# R601X.net
KiCad netlist of a schematic drawn in EAGLE
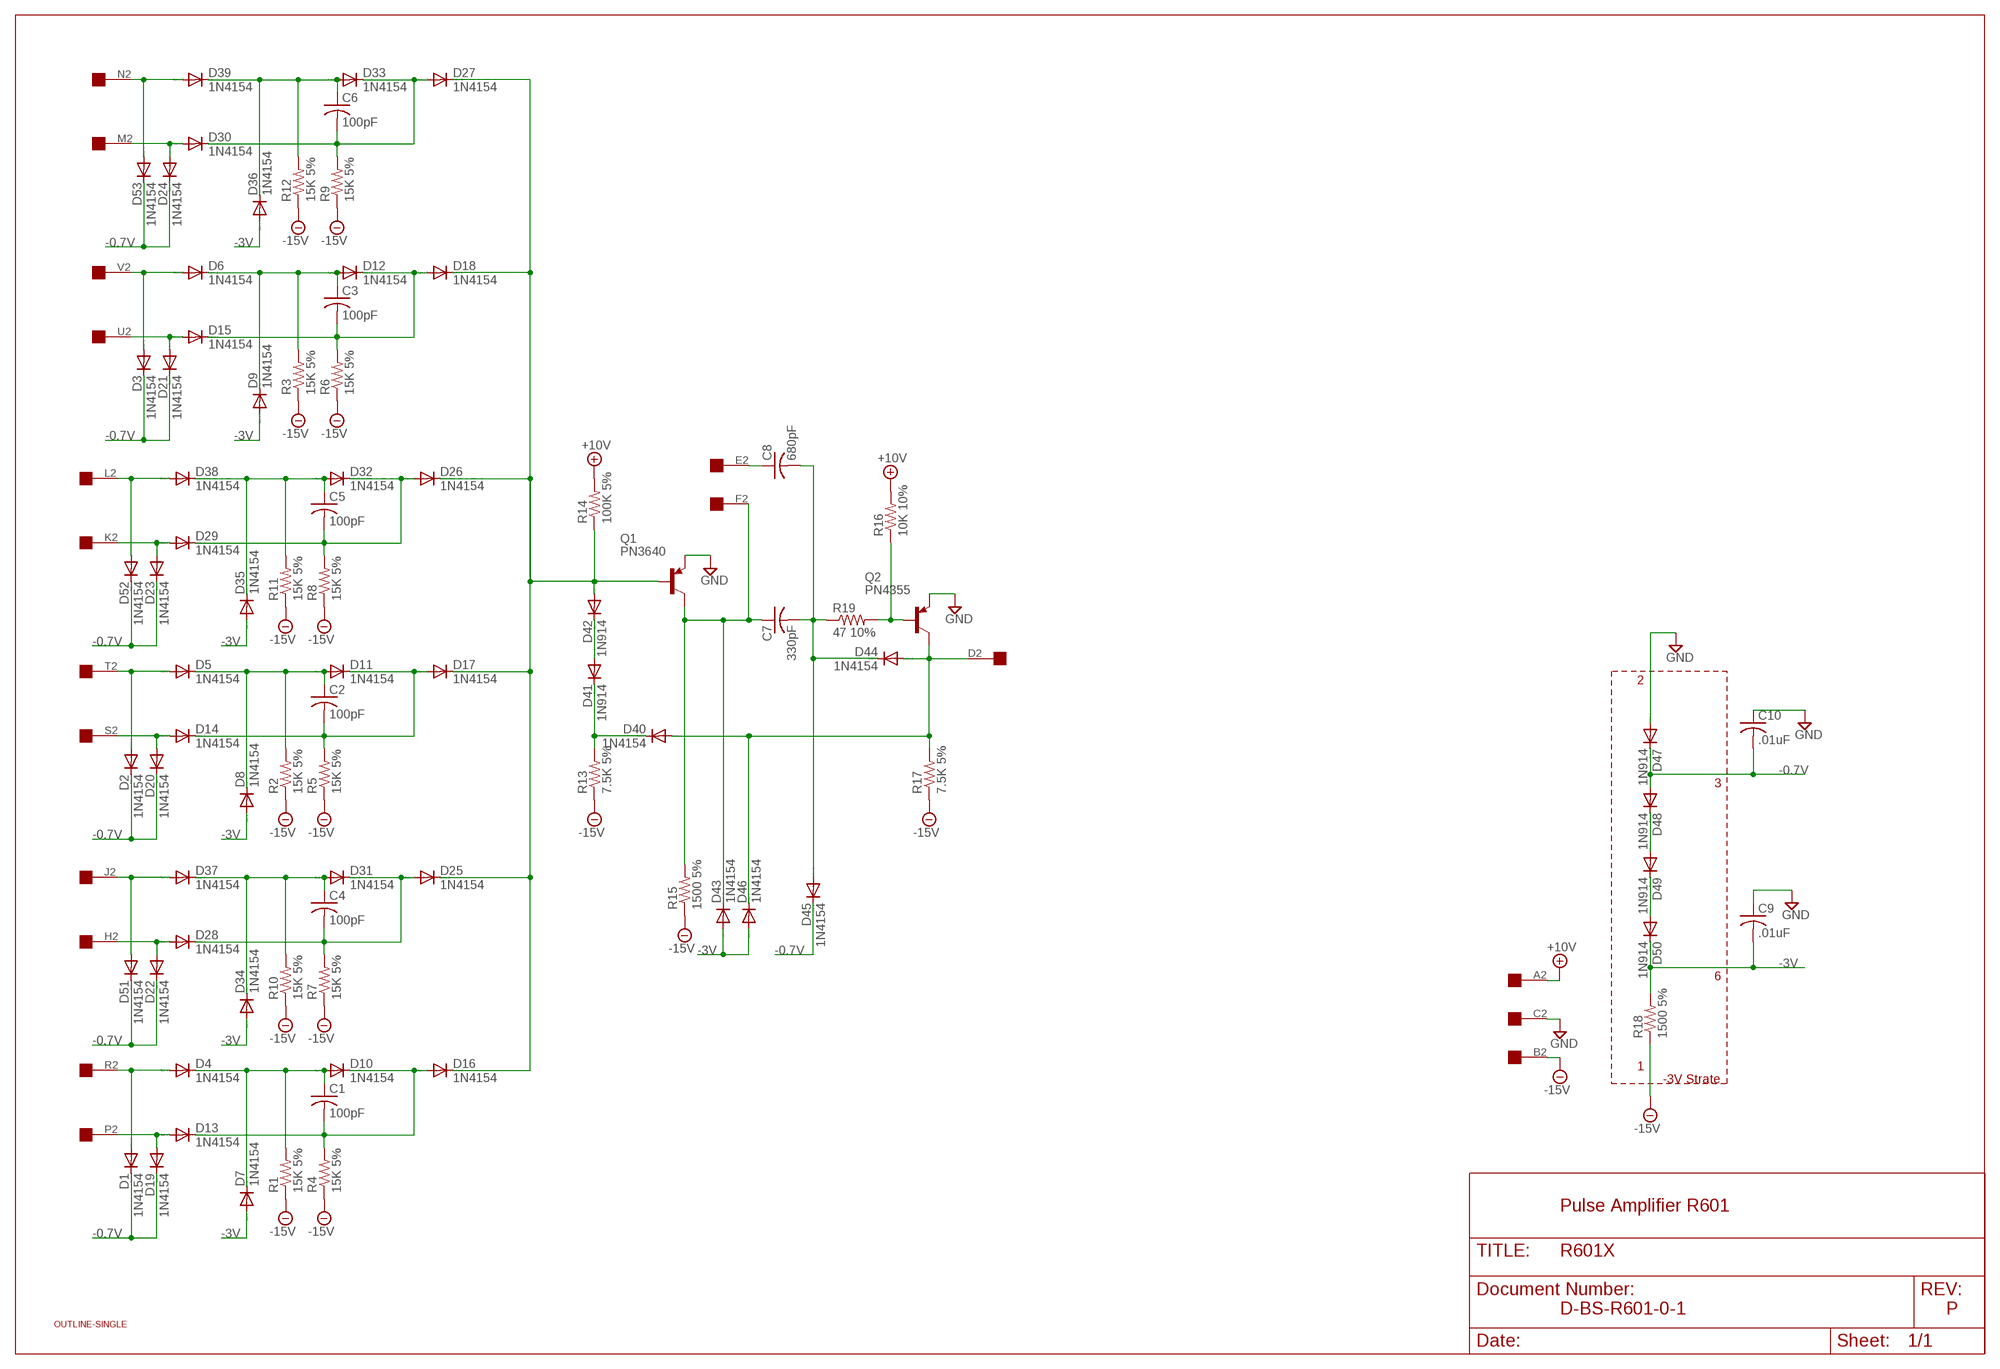
[diagram p0: schematic, sheet 1]

(export (version "E")
  (design (tool "Eeschema 10.0.6"))
  (components
    (comp (ref "C1")
      (value "100pF")
      (footprint "eagle-import:C050-025X075")
      (libsource (lib "eagle-import") (part "C-US050-025X075"))
    )
    (comp (ref "C2")
      (value "100pF")
      (footprint "eagle-import:C050-025X075")
      (libsource (lib "eagle-import") (part "C-US050-025X075"))
    )
    (comp (ref "C3")
      (value "100pF")
      (footprint "eagle-import:C050-025X075")
      (libsource (lib "eagle-import") (part "C-US050-025X075"))
    )
    (comp (ref "C4")
      (value "100pF")
      (footprint "eagle-import:C050-025X075")
      (libsource (lib "eagle-import") (part "C-US050-025X075"))
    )
    (comp (ref "C5")
      (value "100pF")
      (footprint "eagle-import:C050-025X075")
      (libsource (lib "eagle-import") (part "C-US050-025X075"))
    )
    (comp (ref "C6")
      (value "100pF")
      (footprint "eagle-import:C050-025X075")
      (libsource (lib "eagle-import") (part "C-US050-025X075"))
    )
    (comp (ref "C7")
      (value "330pF")
      (footprint "eagle-import:C050-025X075")
      (libsource (lib "eagle-import") (part "C-US050-025X075"))
    )
    (comp (ref "C8")
      (value "680pF")
      (footprint "eagle-import:C050-025X075")
      (libsource (lib "eagle-import") (part "C-US050-025X075"))
    )
    (comp (ref "C9")
      (value ".01uF")
      (footprint "eagle-import:C050-025X075")
      (libsource (lib "eagle-import") (part "C-US050-025X075"))
    )
    (comp (ref "C10")
      (value ".01uF")
      (footprint "eagle-import:C050-025X075")
      (libsource (lib "eagle-import") (part "C-US050-025X075"))
    )
    (comp (ref "D1")
      (value "1N4154")
      (footprint "eagle-import:DO35-10")
      (libsource (lib "eagle-import") (part "1N4148DO35-10"))
    )
    (comp (ref "D2")
      (value "1N4154")
      (footprint "eagle-import:DO35-10")
      (libsource (lib "eagle-import") (part "1N4148DO35-10"))
    )
    (comp (ref "D3")
      (value "1N4154")
      (footprint "eagle-import:DO35-10")
      (libsource (lib "eagle-import") (part "1N4148DO35-10"))
    )
    (comp (ref "D4")
      (value "1N4154")
      (footprint "eagle-import:DO35-10")
      (libsource (lib "eagle-import") (part "1N4148DO35-10"))
    )
    (comp (ref "D5")
      (value "1N4154")
      (footprint "eagle-import:DO35-10")
      (libsource (lib "eagle-import") (part "1N4148DO35-10"))
    )
    (comp (ref "D6")
      (value "1N4154")
      (footprint "eagle-import:DO35-10")
      (libsource (lib "eagle-import") (part "1N4148DO35-10"))
    )
    (comp (ref "D7")
      (value "1N4154")
      (footprint "eagle-import:DO35-10")
      (libsource (lib "eagle-import") (part "1N4148DO35-10"))
    )
    (comp (ref "D8")
      (value "1N4154")
      (footprint "eagle-import:DO35-10")
      (libsource (lib "eagle-import") (part "1N4148DO35-10"))
    )
    (comp (ref "D9")
      (value "1N4154")
      (footprint "eagle-import:DO35-10")
      (libsource (lib "eagle-import") (part "1N4148DO35-10"))
    )
    (comp (ref "D10")
      (value "1N4154")
      (footprint "eagle-import:DO35-10")
      (libsource (lib "eagle-import") (part "1N4148DO35-10"))
    )
    (comp (ref "D11")
      (value "1N4154")
      (footprint "eagle-import:DO35-10")
      (libsource (lib "eagle-import") (part "1N4148DO35-10"))
    )
    (comp (ref "D12")
      (value "1N4154")
      (footprint "eagle-import:DO35-10")
      (libsource (lib "eagle-import") (part "1N4148DO35-10"))
    )
    (comp (ref "D13")
      (value "1N4154")
      (footprint "eagle-import:DO35-10")
      (libsource (lib "eagle-import") (part "1N4148DO35-10"))
    )
    (comp (ref "D14")
      (value "1N4154")
      (footprint "eagle-import:DO35-10")
      (libsource (lib "eagle-import") (part "1N4148DO35-10"))
    )
    (comp (ref "D15")
      (value "1N4154")
      (footprint "eagle-import:DO35-10")
      (libsource (lib "eagle-import") (part "1N4148DO35-10"))
    )
    (comp (ref "D16")
      (value "1N4154")
      (footprint "eagle-import:DO35-10")
      (libsource (lib "eagle-import") (part "1N4148DO35-10"))
    )
    (comp (ref "D17")
      (value "1N4154")
      (footprint "eagle-import:DO35-10")
      (libsource (lib "eagle-import") (part "1N4148DO35-10"))
    )
    (comp (ref "D18")
      (value "1N4154")
      (footprint "eagle-import:DO35-10")
      (libsource (lib "eagle-import") (part "1N4148DO35-10"))
    )
    (comp (ref "D19")
      (value "1N4154")
      (footprint "eagle-import:DO35-10")
      (libsource (lib "eagle-import") (part "1N4148DO35-10"))
    )
    (comp (ref "D20")
      (value "1N4154")
      (footprint "eagle-import:DO35-10")
      (libsource (lib "eagle-import") (part "1N4148DO35-10"))
    )
    (comp (ref "D21")
      (value "1N4154")
      (footprint "eagle-import:DO35-10")
      (libsource (lib "eagle-import") (part "1N4148DO35-10"))
    )
    (comp (ref "D22")
      (value "1N4154")
      (footprint "eagle-import:DO35-10")
      (libsource (lib "eagle-import") (part "1N4148DO35-10"))
    )
    (comp (ref "D23")
      (value "1N4154")
      (footprint "eagle-import:DO35-10")
      (libsource (lib "eagle-import") (part "1N4148DO35-10"))
    )
    (comp (ref "D24")
      (value "1N4154")
      (footprint "eagle-import:DO35-10")
      (libsource (lib "eagle-import") (part "1N4148DO35-10"))
    )
    (comp (ref "D25")
      (value "1N4154")
      (footprint "eagle-import:DO35-10")
      (libsource (lib "eagle-import") (part "1N4148DO35-10"))
    )
    (comp (ref "D26")
      (value "1N4154")
      (footprint "eagle-import:DO35-10")
      (libsource (lib "eagle-import") (part "1N4148DO35-10"))
    )
    (comp (ref "D27")
      (value "1N4154")
      (footprint "eagle-import:DO35-10")
      (libsource (lib "eagle-import") (part "1N4148DO35-10"))
    )
    (comp (ref "D28")
      (value "1N4154")
      (footprint "eagle-import:DO35-10")
      (libsource (lib "eagle-import") (part "1N4148DO35-10"))
    )
    (comp (ref "D29")
      (value "1N4154")
      (footprint "eagle-import:DO35-10")
      (libsource (lib "eagle-import") (part "1N4148DO35-10"))
    )
    (comp (ref "D30")
      (value "1N4154")
      (footprint "eagle-import:DO35-10")
      (libsource (lib "eagle-import") (part "1N4148DO35-10"))
    )
    (comp (ref "D31")
      (value "1N4154")
      (footprint "eagle-import:DO35-10")
      (libsource (lib "eagle-import") (part "1N4148DO35-10"))
    )
    (comp (ref "D32")
      (value "1N4154")
      (footprint "eagle-import:DO35-10")
      (libsource (lib "eagle-import") (part "1N4148DO35-10"))
    )
    (comp (ref "D33")
      (value "1N4154")
      (footprint "eagle-import:DO35-10")
      (libsource (lib "eagle-import") (part "1N4148DO35-10"))
    )
    (comp (ref "D34")
      (value "1N4154")
      (footprint "eagle-import:DO35-10")
      (libsource (lib "eagle-import") (part "1N4148DO35-10"))
    )
    (comp (ref "D35")
      (value "1N4154")
      (footprint "eagle-import:DO35-10")
      (libsource (lib "eagle-import") (part "1N4148DO35-10"))
    )
    (comp (ref "D36")
      (value "1N4154")
      (footprint "eagle-import:DO35-10")
      (libsource (lib "eagle-import") (part "1N4148DO35-10"))
    )
    (comp (ref "D37")
      (value "1N4154")
      (footprint "eagle-import:DO35-10")
      (libsource (lib "eagle-import") (part "1N4148DO35-10"))
    )
    (comp (ref "D38")
      (value "1N4154")
      (footprint "eagle-import:DO35-10")
      (libsource (lib "eagle-import") (part "1N4148DO35-10"))
    )
    (comp (ref "D39")
      (value "1N4154")
      (footprint "eagle-import:DO35-10")
      (libsource (lib "eagle-import") (part "1N4148DO35-10"))
    )
    (comp (ref "D40")
      (value "1N4154")
      (footprint "eagle-import:DO35-10")
      (libsource (lib "eagle-import") (part "1N4148DO35-10"))
    )
    (comp (ref "D41")
      (value "1N914")
      (footprint "eagle-import:DO35-10")
      (libsource (lib "eagle-import") (part "1N4148DO35-10"))
    )
    (comp (ref "D42")
      (value "1N914")
      (footprint "eagle-import:DO35-10")
      (libsource (lib "eagle-import") (part "1N4148DO35-10"))
    )
    (comp (ref "D43")
      (value "1N4154")
      (footprint "eagle-import:DO35-10")
      (libsource (lib "eagle-import") (part "1N4148DO35-10"))
    )
    (comp (ref "D44")
      (value "1N4154")
      (footprint "eagle-import:DO35-10")
      (libsource (lib "eagle-import") (part "1N4148DO35-10"))
    )
    (comp (ref "D45")
      (value "1N4154")
      (footprint "eagle-import:DO35-10")
      (libsource (lib "eagle-import") (part "1N4148DO35-10"))
    )
    (comp (ref "D46")
      (value "1N4154")
      (footprint "eagle-import:DO35-10")
      (libsource (lib "eagle-import") (part "1N4148DO35-10"))
    )
    (comp (ref "D47")
      (value "1N914")
      (footprint "eagle-import:DO35-10")
      (libsource (lib "eagle-import") (part "1N4148DO35-10"))
    )
    (comp (ref "D48")
      (value "1N914")
      (footprint "eagle-import:DO35-10")
      (libsource (lib "eagle-import") (part "1N4148DO35-10"))
    )
    (comp (ref "D49")
      (value "1N914")
      (footprint "eagle-import:DO35-10")
      (libsource (lib "eagle-import") (part "1N4148DO35-10"))
    )
    (comp (ref "D50")
      (value "1N914")
      (footprint "eagle-import:DO35-10")
      (libsource (lib "eagle-import") (part "1N4148DO35-10"))
    )
    (comp (ref "D51")
      (value "1N4154")
      (footprint "eagle-import:DO35-10")
      (libsource (lib "eagle-import") (part "1N4148DO35-10"))
    )
    (comp (ref "D52")
      (value "1N4154")
      (footprint "eagle-import:DO35-10")
      (libsource (lib "eagle-import") (part "1N4148DO35-10"))
    )
    (comp (ref "D53")
      (value "1N4154")
      (footprint "eagle-import:DO35-10")
      (libsource (lib "eagle-import") (part "1N4148DO35-10"))
    )
    (comp (ref "Q1")
      (value "PN3640")
      (footprint "eagle-import:TO39")
      (libsource (lib "eagle-import") (part "2N2904"))
    )
    (comp (ref "Q2")
      (value "PN4355")
      (footprint "eagle-import:TO39")
      (libsource (lib "eagle-import") (part "2N2904"))
    )
    (comp (ref "R1")
      (value "15K 5%")
      (footprint "eagle-import:0207_10")
      (libsource (lib "eagle-import") (part "R-US_0207/10"))
    )
    (comp (ref "R2")
      (value "15K 5%")
      (footprint "eagle-import:0207_10")
      (libsource (lib "eagle-import") (part "R-US_0207/10"))
    )
    (comp (ref "R3")
      (value "15K 5%")
      (footprint "eagle-import:0207_10")
      (libsource (lib "eagle-import") (part "R-US_0207/10"))
    )
    (comp (ref "R4")
      (value "15K 5%")
      (footprint "eagle-import:0207_10")
      (libsource (lib "eagle-import") (part "R-US_0207/10"))
    )
    (comp (ref "R5")
      (value "15K 5%")
      (footprint "eagle-import:0207_10")
      (libsource (lib "eagle-import") (part "R-US_0207/10"))
    )
    (comp (ref "R6")
      (value "15K 5%")
      (footprint "eagle-import:0207_10")
      (libsource (lib "eagle-import") (part "R-US_0207/10"))
    )
    (comp (ref "R7")
      (value "15K 5%")
      (footprint "eagle-import:0207_10")
      (libsource (lib "eagle-import") (part "R-US_0207/10"))
    )
    (comp (ref "R8")
      (value "15K 5%")
      (footprint "eagle-import:0207_10")
      (libsource (lib "eagle-import") (part "R-US_0207/10"))
    )
    (comp (ref "R9")
      (value "15K 5%")
      (footprint "eagle-import:0207_10")
      (libsource (lib "eagle-import") (part "R-US_0207/10"))
    )
    (comp (ref "R10")
      (value "15K 5%")
      (footprint "eagle-import:0207_10")
      (libsource (lib "eagle-import") (part "R-US_0207/10"))
    )
    (comp (ref "R11")
      (value "15K 5%")
      (footprint "eagle-import:0207_10")
      (libsource (lib "eagle-import") (part "R-US_0207/10"))
    )
    (comp (ref "R12")
      (value "15K 5%")
      (footprint "eagle-import:0207_10")
      (libsource (lib "eagle-import") (part "R-US_0207/10"))
    )
    (comp (ref "R13")
      (value "7.5K 5%")
      (footprint "eagle-import:0207_10")
      (libsource (lib "eagle-import") (part "R-US_0207/10"))
    )
    (comp (ref "R14")
      (value "100K 5%")
      (footprint "eagle-import:0207_10")
      (libsource (lib "eagle-import") (part "R-US_0207/10"))
    )
    (comp (ref "R15")
      (value "1500 5%")
      (footprint "eagle-import:0207_10")
      (libsource (lib "eagle-import") (part "R-US_0207/10"))
    )
    (comp (ref "R16")
      (value "10K 10%")
      (footprint "eagle-import:0207_10")
      (libsource (lib "eagle-import") (part "R-US_0207/10"))
    )
    (comp (ref "R17")
      (value "7.5K 5%")
      (footprint "eagle-import:0207_10")
      (libsource (lib "eagle-import") (part "R-US_0207/10"))
    )
    (comp (ref "R18")
      (value "1500 5%")
      (footprint "eagle-import:0207_10")
      (libsource (lib "eagle-import") (part "R-US_0207/10"))
    )
    (comp (ref "R19")
      (value "47 10%")
      (footprint "eagle-import:0207_10")
      (libsource (lib "eagle-import") (part "R-US_0207/10"))
    )
    (comp (ref "U$1")
      (value "OUTLINE-SINGLE")
      (footprint "eagle-import:SINGLE")
      (libsource (lib "eagle-import") (part "OUTLINE-SINGLE"))
    )
    (comp (ref "U$2")
      (value "EDGE-1")
      (footprint "eagle-import:EDGE-CON1")
      (libsource (lib "eagle-import") (part "EDGE-1"))
    )
  )
  (nets
    (net (code "1") (name "+10V") (class "Default")
      (node (ref "R14") (pin "2") (pinfunction "2_2") (pintype "passive"))
      (node (ref "R16") (pin "2") (pinfunction "2_2") (pintype "passive"))
      (node (ref "U$2") (pin "A2") (pinfunction "1_A2") (pintype "bidirectional"))
    )
    (net (code "2") (name "-15V") (class "Default")
      (node (ref "R1") (pin "1") (pinfunction "1_1") (pintype "passive"))
      (node (ref "R10") (pin "1") (pinfunction "1_1") (pintype "passive"))
      (node (ref "R11") (pin "1") (pinfunction "1_1") (pintype "passive"))
      (node (ref "R12") (pin "1") (pinfunction "1_1") (pintype "passive"))
      (node (ref "R13") (pin "1") (pinfunction "1_1") (pintype "passive"))
      (node (ref "R15") (pin "1") (pinfunction "1_1") (pintype "passive"))
      (node (ref "R17") (pin "1") (pinfunction "1_1") (pintype "passive"))
      (node (ref "R18") (pin "1") (pinfunction "1_1") (pintype "passive"))
      (node (ref "R2") (pin "1") (pinfunction "1_1") (pintype "passive"))
      (node (ref "R3") (pin "1") (pinfunction "1_1") (pintype "passive"))
      (node (ref "R4") (pin "1") (pinfunction "1_1") (pintype "passive"))
      (node (ref "R5") (pin "1") (pinfunction "1_1") (pintype "passive"))
      (node (ref "R6") (pin "1") (pinfunction "1_1") (pintype "passive"))
      (node (ref "R7") (pin "1") (pinfunction "1_1") (pintype "passive"))
      (node (ref "R8") (pin "1") (pinfunction "1_1") (pintype "passive"))
      (node (ref "R9") (pin "1") (pinfunction "1_1") (pintype "passive"))
      (node (ref "U$2") (pin "B2") (pinfunction "1_B2") (pintype "bidirectional"))
    )
    (net (code "3") (name "/-0.7V") (class "Default")
      (node (ref "C10") (pin "2") (pinfunction "2_2") (pintype "passive"))
      (node (ref "D1") (pin "C") (pinfunction "C_C") (pintype "passive"))
      (node (ref "D19") (pin "C") (pinfunction "C_C") (pintype "passive"))
      (node (ref "D2") (pin "C") (pinfunction "C_C") (pintype "passive"))
      (node (ref "D20") (pin "C") (pinfunction "C_C") (pintype "passive"))
      (node (ref "D21") (pin "C") (pinfunction "C_C") (pintype "passive"))
      (node (ref "D22") (pin "C") (pinfunction "C_C") (pintype "passive"))
      (node (ref "D23") (pin "C") (pinfunction "C_C") (pintype "passive"))
      (node (ref "D24") (pin "C") (pinfunction "C_C") (pintype "passive"))
      (node (ref "D3") (pin "C") (pinfunction "C_C") (pintype "passive"))
      (node (ref "D45") (pin "C") (pinfunction "C_C") (pintype "passive"))
      (node (ref "D47") (pin "C") (pinfunction "C_C") (pintype "passive"))
      (node (ref "D48") (pin "A") (pinfunction "A_A") (pintype "passive"))
      (node (ref "D51") (pin "C") (pinfunction "C_C") (pintype "passive"))
      (node (ref "D52") (pin "C") (pinfunction "C_C") (pintype "passive"))
      (node (ref "D53") (pin "C") (pinfunction "C_C") (pintype "passive"))
    )
    (net (code "4") (name "/-3V") (class "Default")
      (node (ref "C9") (pin "2") (pinfunction "2_2") (pintype "passive"))
      (node (ref "D34") (pin "A") (pinfunction "A_A") (pintype "passive"))
      (node (ref "D35") (pin "A") (pinfunction "A_A") (pintype "passive"))
      (node (ref "D36") (pin "A") (pinfunction "A_A") (pintype "passive"))
      (node (ref "D43") (pin "A") (pinfunction "A_A") (pintype "passive"))
      (node (ref "D46") (pin "A") (pinfunction "A_A") (pintype "passive"))
      (node (ref "D50") (pin "C") (pinfunction "C_C") (pintype "passive"))
      (node (ref "D7") (pin "A") (pinfunction "A_A") (pintype "passive"))
      (node (ref "D8") (pin "A") (pinfunction "A_A") (pintype "passive"))
      (node (ref "D9") (pin "A") (pinfunction "A_A") (pintype "passive"))
      (node (ref "R18") (pin "2") (pinfunction "2_2") (pintype "passive"))
    )
    (net (code "5") (name "GND") (class "Default")
      (node (ref "C10") (pin "1") (pinfunction "1_1") (pintype "passive"))
      (node (ref "C9") (pin "1") (pinfunction "1_1") (pintype "passive"))
      (node (ref "D47") (pin "A") (pinfunction "A_A") (pintype "passive"))
      (node (ref "Q1") (pin "1") (pinfunction "E_1") (pintype "passive"))
      (node (ref "Q2") (pin "1") (pinfunction "E_1") (pintype "passive"))
      (node (ref "U$2") (pin "C2") (pinfunction "1_C2") (pintype "bidirectional"))
    )
    (net (code "6") (name "Net-(C1-Pad1)") (class "Default")
      (node (ref "C1") (pin "1") (pinfunction "1_1") (pintype "passive"))
      (node (ref "D10") (pin "A") (pinfunction "A_A") (pintype "passive"))
      (node (ref "D4") (pin "C") (pinfunction "C_C") (pintype "passive"))
      (node (ref "D7") (pin "C") (pinfunction "C_C") (pintype "passive"))
      (node (ref "R1") (pin "2") (pinfunction "2_2") (pintype "passive"))
    )
    (net (code "7") (name "Net-(C1-Pad2)") (class "Default")
      (node (ref "C1") (pin "2") (pinfunction "2_2") (pintype "passive"))
      (node (ref "D10") (pin "C") (pinfunction "C_C") (pintype "passive"))
      (node (ref "D13") (pin "C") (pinfunction "C_C") (pintype "passive"))
      (node (ref "D16") (pin "A") (pinfunction "A_A") (pintype "passive"))
      (node (ref "R4") (pin "2") (pinfunction "2_2") (pintype "passive"))
    )
    (net (code "8") (name "Net-(C2-Pad1)") (class "Default")
      (node (ref "C2") (pin "1") (pinfunction "1_1") (pintype "passive"))
      (node (ref "D11") (pin "A") (pinfunction "A_A") (pintype "passive"))
      (node (ref "D5") (pin "C") (pinfunction "C_C") (pintype "passive"))
      (node (ref "D8") (pin "C") (pinfunction "C_C") (pintype "passive"))
      (node (ref "R2") (pin "2") (pinfunction "2_2") (pintype "passive"))
    )
    (net (code "9") (name "Net-(C2-Pad2)") (class "Default")
      (node (ref "C2") (pin "2") (pinfunction "2_2") (pintype "passive"))
      (node (ref "D11") (pin "C") (pinfunction "C_C") (pintype "passive"))
      (node (ref "D14") (pin "C") (pinfunction "C_C") (pintype "passive"))
      (node (ref "D17") (pin "A") (pinfunction "A_A") (pintype "passive"))
      (node (ref "R5") (pin "2") (pinfunction "2_2") (pintype "passive"))
    )
    (net (code "10") (name "Net-(C3-Pad1)") (class "Default")
      (node (ref "C3") (pin "1") (pinfunction "1_1") (pintype "passive"))
      (node (ref "D12") (pin "A") (pinfunction "A_A") (pintype "passive"))
      (node (ref "D6") (pin "C") (pinfunction "C_C") (pintype "passive"))
      (node (ref "D9") (pin "C") (pinfunction "C_C") (pintype "passive"))
      (node (ref "R3") (pin "2") (pinfunction "2_2") (pintype "passive"))
    )
    (net (code "11") (name "Net-(C3-Pad2)") (class "Default")
      (node (ref "C3") (pin "2") (pinfunction "2_2") (pintype "passive"))
      (node (ref "D12") (pin "C") (pinfunction "C_C") (pintype "passive"))
      (node (ref "D15") (pin "C") (pinfunction "C_C") (pintype "passive"))
      (node (ref "D18") (pin "A") (pinfunction "A_A") (pintype "passive"))
      (node (ref "R6") (pin "2") (pinfunction "2_2") (pintype "passive"))
    )
    (net (code "12") (name "Net-(C4-Pad1)") (class "Default")
      (node (ref "C4") (pin "1") (pinfunction "1_1") (pintype "passive"))
      (node (ref "D31") (pin "A") (pinfunction "A_A") (pintype "passive"))
      (node (ref "D34") (pin "C") (pinfunction "C_C") (pintype "passive"))
      (node (ref "D37") (pin "C") (pinfunction "C_C") (pintype "passive"))
      (node (ref "R10") (pin "2") (pinfunction "2_2") (pintype "passive"))
    )
    (net (code "13") (name "Net-(C4-Pad2)") (class "Default")
      (node (ref "C4") (pin "2") (pinfunction "2_2") (pintype "passive"))
      (node (ref "D25") (pin "A") (pinfunction "A_A") (pintype "passive"))
      (node (ref "D28") (pin "C") (pinfunction "C_C") (pintype "passive"))
      (node (ref "D31") (pin "C") (pinfunction "C_C") (pintype "passive"))
      (node (ref "R7") (pin "2") (pinfunction "2_2") (pintype "passive"))
    )
    (net (code "14") (name "Net-(C5-Pad1)") (class "Default")
      (node (ref "C5") (pin "1") (pinfunction "1_1") (pintype "passive"))
      (node (ref "D32") (pin "A") (pinfunction "A_A") (pintype "passive"))
      (node (ref "D35") (pin "C") (pinfunction "C_C") (pintype "passive"))
      (node (ref "D38") (pin "C") (pinfunction "C_C") (pintype "passive"))
      (node (ref "R11") (pin "2") (pinfunction "2_2") (pintype "passive"))
    )
    (net (code "15") (name "Net-(C5-Pad2)") (class "Default")
      (node (ref "C5") (pin "2") (pinfunction "2_2") (pintype "passive"))
      (node (ref "D26") (pin "A") (pinfunction "A_A") (pintype "passive"))
      (node (ref "D29") (pin "C") (pinfunction "C_C") (pintype "passive"))
      (node (ref "D32") (pin "C") (pinfunction "C_C") (pintype "passive"))
      (node (ref "R8") (pin "2") (pinfunction "2_2") (pintype "passive"))
    )
    (net (code "16") (name "Net-(C6-Pad1)") (class "Default")
      (node (ref "C6") (pin "1") (pinfunction "1_1") (pintype "passive"))
      (node (ref "D33") (pin "A") (pinfunction "A_A") (pintype "passive"))
      (node (ref "D36") (pin "C") (pinfunction "C_C") (pintype "passive"))
      (node (ref "D39") (pin "C") (pinfunction "C_C") (pintype "passive"))
      (node (ref "R12") (pin "2") (pinfunction "2_2") (pintype "passive"))
    )
    (net (code "17") (name "Net-(C6-Pad2)") (class "Default")
      (node (ref "C6") (pin "2") (pinfunction "2_2") (pintype "passive"))
      (node (ref "D27") (pin "A") (pinfunction "A_A") (pintype "passive"))
      (node (ref "D30") (pin "C") (pinfunction "C_C") (pintype "passive"))
      (node (ref "D33") (pin "C") (pinfunction "C_C") (pintype "passive"))
      (node (ref "R9") (pin "2") (pinfunction "2_2") (pintype "passive"))
    )
    (net (code "18") (name "Net-(C7-Pad2)") (class "Default")
      (node (ref "C7") (pin "2") (pinfunction "2_2") (pintype "passive"))
      (node (ref "C8") (pin "2") (pinfunction "2_2") (pintype "passive"))
      (node (ref "D44") (pin "C") (pinfunction "C_C") (pintype "passive"))
      (node (ref "D45") (pin "A") (pinfunction "A_A") (pintype "passive"))
      (node (ref "R19") (pin "1") (pinfunction "1_1") (pintype "passive"))
    )
    (net (code "19") (name "Net-(D40-PadC)") (class "Default")
      (node (ref "D40") (pin "C") (pinfunction "C_C") (pintype "passive"))
      (node (ref "D41") (pin "C") (pinfunction "C_C") (pintype "passive"))
      (node (ref "R13") (pin "2") (pinfunction "2_2") (pintype "passive"))
    )
    (net (code "20") (name "Net-(D41-PadA)") (class "Default")
      (node (ref "D41") (pin "A") (pinfunction "A_A") (pintype "passive"))
      (node (ref "D42") (pin "C") (pinfunction "C_C") (pintype "passive"))
    )
    (net (code "21") (name "Net-(D48-PadC)") (class "Default")
      (node (ref "D48") (pin "C") (pinfunction "C_C") (pintype "passive"))
      (node (ref "D49") (pin "A") (pinfunction "A_A") (pintype "passive"))
    )
    (net (code "22") (name "Net-(D49-PadC)") (class "Default")
      (node (ref "D49") (pin "C") (pinfunction "C_C") (pintype "passive"))
      (node (ref "D50") (pin "A") (pinfunction "A_A") (pintype "passive"))
    )
    (net (code "23") (name "Net-(Q1-B)") (class "Default")
      (node (ref "D16") (pin "C") (pinfunction "C_C") (pintype "passive"))
      (node (ref "D17") (pin "C") (pinfunction "C_C") (pintype "passive"))
      (node (ref "D18") (pin "C") (pinfunction "C_C") (pintype "passive"))
      (node (ref "D25") (pin "C") (pinfunction "C_C") (pintype "passive"))
      (node (ref "D26") (pin "C") (pinfunction "C_C") (pintype "passive"))
      (node (ref "D27") (pin "C") (pinfunction "C_C") (pintype "passive"))
      (node (ref "D42") (pin "A") (pinfunction "A_A") (pintype "passive"))
      (node (ref "Q1") (pin "2") (pinfunction "B_2") (pintype "passive"))
      (node (ref "R14") (pin "1") (pinfunction "1_1") (pintype "passive"))
    )
    (net (code "24") (name "Net-(Q1-C)") (class "Default")
      (node (ref "C7") (pin "1") (pinfunction "1_1") (pintype "passive"))
      (node (ref "D43") (pin "C") (pinfunction "C_C") (pintype "passive"))
      (node (ref "Q1") (pin "3") (pinfunction "C_3") (pintype "passive"))
      (node (ref "R15") (pin "2") (pinfunction "2_2") (pintype "passive"))
      (node (ref "U$2") (pin "F2") (pinfunction "1_F2") (pintype "bidirectional"))
    )
    (net (code "25") (name "Net-(Q2-B)") (class "Default")
      (node (ref "Q2") (pin "2") (pinfunction "B_2") (pintype "passive"))
      (node (ref "R16") (pin "1") (pinfunction "1_1") (pintype "passive"))
      (node (ref "R19") (pin "2") (pinfunction "2_2") (pintype "passive"))
    )
    (net (code "26") (name "Net-(Q2-C)") (class "Default")
      (node (ref "D40") (pin "A") (pinfunction "A_A") (pintype "passive"))
      (node (ref "D44") (pin "A") (pinfunction "A_A") (pintype "passive"))
      (node (ref "D46") (pin "C") (pinfunction "C_C") (pintype "passive"))
      (node (ref "Q2") (pin "3") (pinfunction "C_3") (pintype "passive"))
      (node (ref "R17") (pin "2") (pinfunction "2_2") (pintype "passive"))
      (node (ref "U$2") (pin "D2") (pinfunction "1_D2") (pintype "bidirectional"))
    )
    (net (code "27") (name "Net-(U$2E-1)") (class "Default")
      (node (ref "C8") (pin "1") (pinfunction "1_1") (pintype "passive"))
      (node (ref "U$2") (pin "E2") (pinfunction "1_E2") (pintype "bidirectional"))
    )
    (net (code "28") (name "Net-(U$2G-1)") (class "Default")
      (node (ref "D22") (pin "A") (pinfunction "A_A") (pintype "passive"))
      (node (ref "D28") (pin "A") (pinfunction "A_A") (pintype "passive"))
      (node (ref "U$2") (pin "H2") (pinfunction "1_H2") (pintype "bidirectional"))
    )
    (net (code "29") (name "Net-(U$2H-1)") (class "Default")
      (node (ref "D37") (pin "A") (pinfunction "A_A") (pintype "passive"))
      (node (ref "D51") (pin "A") (pinfunction "A_A") (pintype "passive"))
      (node (ref "U$2") (pin "J2") (pinfunction "1_J2") (pintype "bidirectional"))
    )
    (net (code "30") (name "Net-(U$2I-1)") (class "Default")
      (node (ref "D23") (pin "A") (pinfunction "A_A") (pintype "passive"))
      (node (ref "D29") (pin "A") (pinfunction "A_A") (pintype "passive"))
      (node (ref "U$2") (pin "K2") (pinfunction "1_K2") (pintype "bidirectional"))
    )
    (net (code "31") (name "Net-(U$2J-1)") (class "Default")
      (node (ref "D38") (pin "A") (pinfunction "A_A") (pintype "passive"))
      (node (ref "D52") (pin "A") (pinfunction "A_A") (pintype "passive"))
      (node (ref "U$2") (pin "L2") (pinfunction "1_L2") (pintype "bidirectional"))
    )
    (net (code "32") (name "Net-(U$2K-1)") (class "Default")
      (node (ref "D24") (pin "A") (pinfunction "A_A") (pintype "passive"))
      (node (ref "D30") (pin "A") (pinfunction "A_A") (pintype "passive"))
      (node (ref "U$2") (pin "M2") (pinfunction "1_M2") (pintype "bidirectional"))
    )
    (net (code "33") (name "Net-(U$2L-1)") (class "Default")
      (node (ref "D39") (pin "A") (pinfunction "A_A") (pintype "passive"))
      (node (ref "D53") (pin "A") (pinfunction "A_A") (pintype "passive"))
      (node (ref "U$2") (pin "N2") (pinfunction "1_N2") (pintype "bidirectional"))
    )
    (net (code "34") (name "Net-(U$2M-1)") (class "Default")
      (node (ref "D13") (pin "A") (pinfunction "A_A") (pintype "passive"))
      (node (ref "D19") (pin "A") (pinfunction "A_A") (pintype "passive"))
      (node (ref "U$2") (pin "P2") (pinfunction "1_P2") (pintype "bidirectional"))
    )
    (net (code "35") (name "Net-(U$2N-1)") (class "Default")
      (node (ref "D1") (pin "A") (pinfunction "A_A") (pintype "passive"))
      (node (ref "D4") (pin "A") (pinfunction "A_A") (pintype "passive"))
      (node (ref "U$2") (pin "R2") (pinfunction "1_R2") (pintype "bidirectional"))
    )
    (net (code "36") (name "Net-(U$2O-1)") (class "Default")
      (node (ref "D14") (pin "A") (pinfunction "A_A") (pintype "passive"))
      (node (ref "D20") (pin "A") (pinfunction "A_A") (pintype "passive"))
      (node (ref "U$2") (pin "S2") (pinfunction "1_S2") (pintype "bidirectional"))
    )
    (net (code "37") (name "Net-(U$2P-1)") (class "Default")
      (node (ref "D2") (pin "A") (pinfunction "A_A") (pintype "passive"))
      (node (ref "D5") (pin "A") (pinfunction "A_A") (pintype "passive"))
      (node (ref "U$2") (pin "T2") (pinfunction "1_T2") (pintype "bidirectional"))
    )
    (net (code "38") (name "Net-(U$2Q-1)") (class "Default")
      (node (ref "D15") (pin "A") (pinfunction "A_A") (pintype "passive"))
      (node (ref "D21") (pin "A") (pinfunction "A_A") (pintype "passive"))
      (node (ref "U$2") (pin "U2") (pinfunction "1_U2") (pintype "bidirectional"))
    )
    (net (code "39") (name "Net-(U$2R-1)") (class "Default")
      (node (ref "D3") (pin "A") (pinfunction "A_A") (pintype "passive"))
      (node (ref "D6") (pin "A") (pinfunction "A_A") (pintype "passive"))
      (node (ref "U$2") (pin "V2") (pinfunction "1_V2") (pintype "bidirectional"))
    )
  )
)
